# schematic_easyeda.net
KiCad netlist of a schematic drawn in EasyEDA
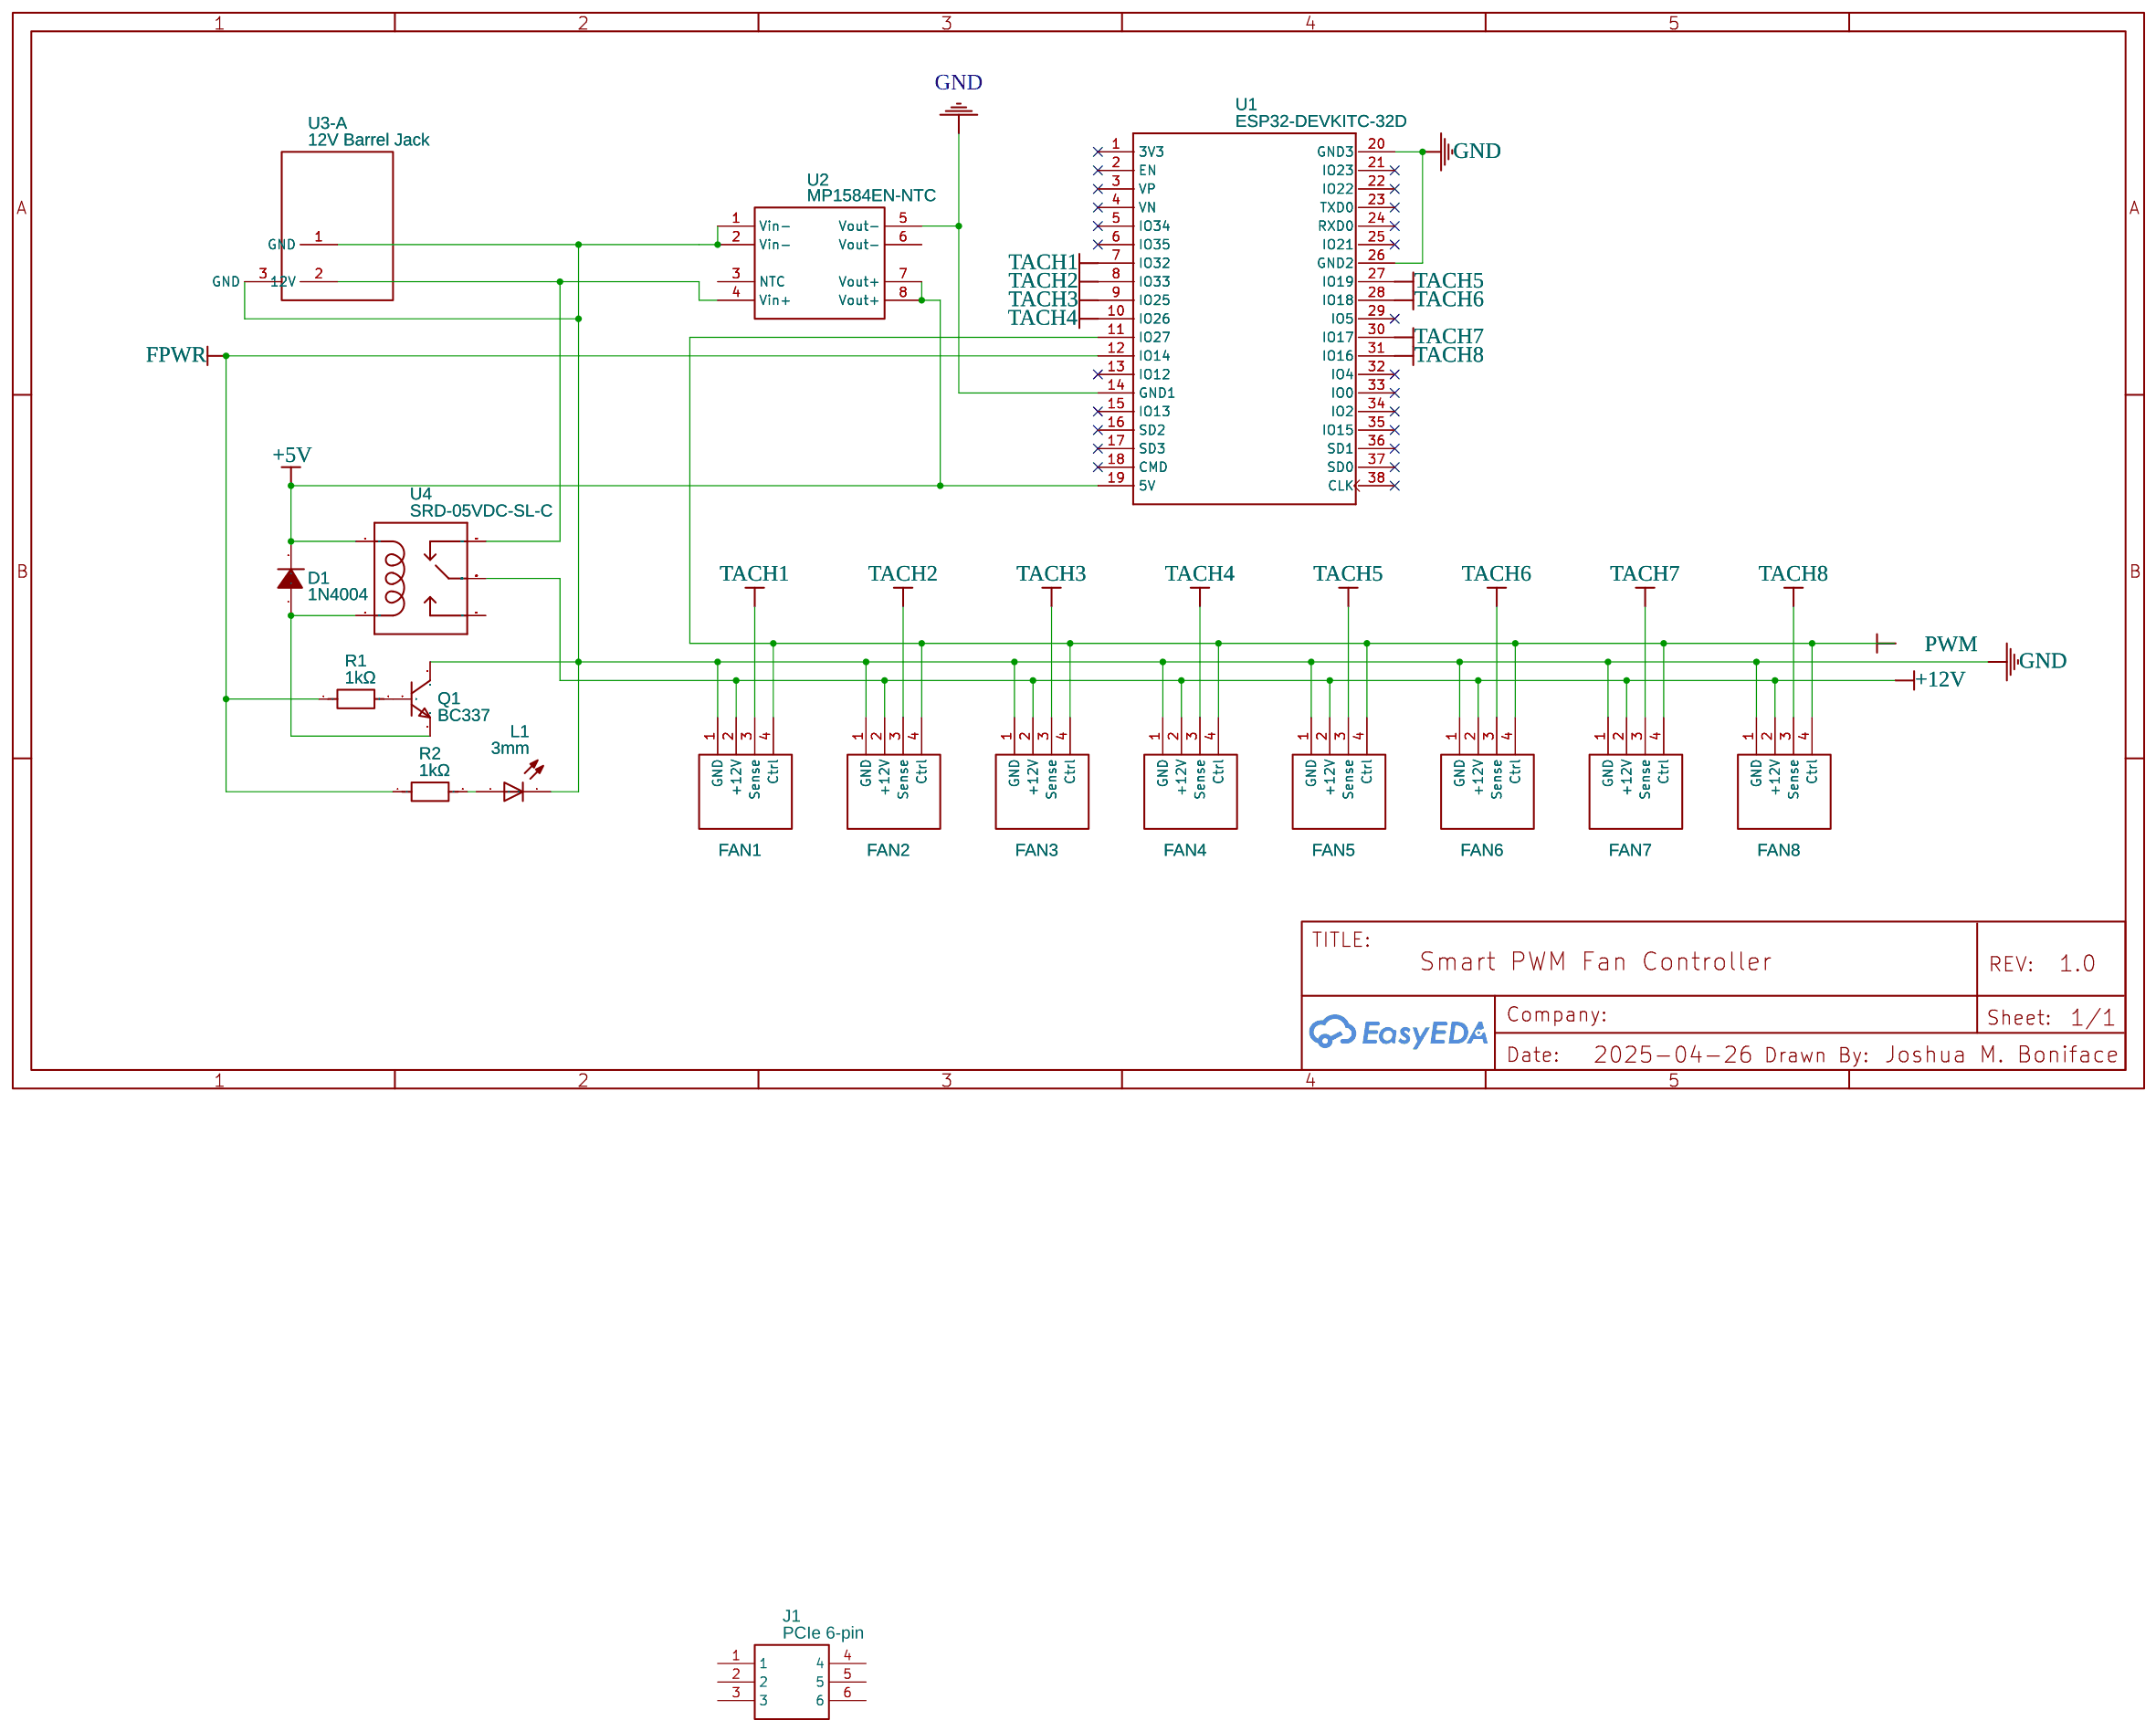
[diagram p0: schematic sheet]

(export (version "E")
  (design (tool "Eeschema 10.0.6"))
  (components
    (comp (ref "D1")
      (value "1N4004")
      (fields (field (name "Manufacturer Part") "1N4007") (field (name "Manufacturer") "ST(先科)"))
      (libsource (lib "") (part "1N4007"))
    )
    (comp (ref "FAN1") (value "4 Pin PWM Fan Header") (libsource (lib "") (part "4 Pin PWM Fan Header")))
    (comp (ref "FAN2") (value "4 Pin PWM Fan Header") (libsource (lib "") (part "4 Pin PWM Fan Header")))
    (comp (ref "FAN3") (value "4 Pin PWM Fan Header") (libsource (lib "") (part "4 Pin PWM Fan Header")))
    (comp (ref "FAN4") (value "4 Pin PWM Fan Header") (libsource (lib "") (part "4 Pin PWM Fan Header")))
    (comp (ref "FAN5") (value "4 Pin PWM Fan Header") (libsource (lib "") (part "4 Pin PWM Fan Header")))
    (comp (ref "FAN6") (value "4 Pin PWM Fan Header") (libsource (lib "") (part "4 Pin PWM Fan Header")))
    (comp (ref "FAN7") (value "4 Pin PWM Fan Header") (libsource (lib "") (part "4 Pin PWM Fan Header")))
    (comp (ref "FAN8") (value "4 Pin PWM Fan Header") (libsource (lib "") (part "4 Pin PWM Fan Header")))
    (comp (ref "J1") (value "PCIe 6-pin") (libsource (lib "") (part "PCIe 6-pin")))
    (comp (ref "L1") (value "3mm") (libsource (lib "") (part "LED 3MM")))
    (comp (ref "Q1")
      (value "BC337")
      (fields (field (name "Manufacturer Part") "2N2222A") (field (name "Manufacturer") "ST(先科)"))
      (libsource (lib "") (part "2N2222"))
    )
    (comp (ref "R1") (value "1kΩ") (libsource (lib "") (part "1/4 W Resistor Vertical")))
    (comp (ref "R2") (value "1kΩ") (libsource (lib "") (part "1/4 W Resistor Vertical")))
    (comp (ref "U1") (value "ESP32-DEVKITC-32D") (libsource (lib "") (part "ESP32-DEVKITC-32D HAT TEMPLATE")))
    (comp (ref "U2")
      (value "MP1584EN-NTC")
      (fields (field (name "Manufacturer Part") "MP1584EN"))
      (libsource (lib "") (part "MP1584EN-NTC COPY"))
    )
    (comp (ref "U3-A") (value "12V Barrel Jack") (libsource (lib "") (part "12V Barrel Jack")))
    (comp (ref "U4") (value "SRD-05VDC-SL-C") (libsource (lib "") (part "12V RELAY")))
  )
  (nets
    (net (code "1") (name "+5V") (class "Default")
      (node (ref "D1") (pin "2") (pinfunction "K_2") (pintype "unspecified"))
      (node (ref "U1") (pin "19") (pinfunction "5V_19") (pintype "bidirectional"))
      (node (ref "U2") (pin "7") (pinfunction "Vout+_7") (pintype "unspecified"))
      (node (ref "U2") (pin "8") (pinfunction "Vout+_8") (pintype "unspecified"))
      (node (ref "U4") (pin "COIL1") (pinfunction "COIL1_COIL1") (pintype "unspecified"))
    )
    (net (code "2") (name "+12V") (class "Default")
      (node (ref "FAN1") (pin "2") (pinfunction "+12V_2") (pintype "unspecified"))
      (node (ref "FAN2") (pin "2") (pinfunction "+12V_2") (pintype "unspecified"))
      (node (ref "FAN3") (pin "2") (pinfunction "+12V_2") (pintype "unspecified"))
      (node (ref "FAN4") (pin "2") (pinfunction "+12V_2") (pintype "unspecified"))
      (node (ref "FAN5") (pin "2") (pinfunction "+12V_2") (pintype "unspecified"))
      (node (ref "FAN6") (pin "2") (pinfunction "+12V_2") (pintype "unspecified"))
      (node (ref "FAN7") (pin "2") (pinfunction "+12V_2") (pintype "unspecified"))
      (node (ref "FAN8") (pin "2") (pinfunction "+12V_2") (pintype "unspecified"))
      (node (ref "U4") (pin "SWCOMMON") (pinfunction "SWCOMMON_SWCOMMON") (pintype "unspecified"))
    )
    (net (code "3") (name "FPWR") (class "Default")
      (node (ref "R1") (pin "1") (pinfunction "1_1") (pintype "unspecified"))
      (node (ref "R2") (pin "1") (pinfunction "1_1") (pintype "unspecified"))
      (node (ref "U1") (pin "12") (pinfunction "IO14_12") (pintype "bidirectional"))
    )
    (net (code "4") (name "GND") (class "Default")
      (node (ref "FAN1") (pin "1") (pinfunction "GND_1") (pintype "unspecified"))
      (node (ref "FAN2") (pin "1") (pinfunction "GND_1") (pintype "unspecified"))
      (node (ref "FAN3") (pin "1") (pinfunction "GND_1") (pintype "unspecified"))
      (node (ref "FAN4") (pin "1") (pinfunction "GND_1") (pintype "unspecified"))
      (node (ref "FAN5") (pin "1") (pinfunction "GND_1") (pintype "unspecified"))
      (node (ref "FAN6") (pin "1") (pinfunction "GND_1") (pintype "unspecified"))
      (node (ref "FAN7") (pin "1") (pinfunction "GND_1") (pintype "unspecified"))
      (node (ref "FAN8") (pin "1") (pinfunction "GND_1") (pintype "unspecified"))
      (node (ref "L1") (pin "K") (pinfunction "2_K") (pintype "unspecified"))
      (node (ref "Q1") (pin "3") (pinfunction "C_3") (pintype "unspecified"))
      (node (ref "U1") (pin "14") (pinfunction "GND1_14") (pintype "bidirectional"))
      (node (ref "U1") (pin "20") (pinfunction "GND3_20") (pintype "bidirectional"))
      (node (ref "U1") (pin "26") (pinfunction "GND2_26") (pintype "bidirectional"))
      (node (ref "U2") (pin "1") (pinfunction "Vin-_1") (pintype "unspecified"))
      (node (ref "U2") (pin "2") (pinfunction "Vin-_2") (pintype "unspecified"))
      (node (ref "U2") (pin "5") (pinfunction "Vout-_5") (pintype "unspecified"))
      (node (ref "U3-A") (pin "1") (pinfunction "GND_1") (pintype "unspecified"))
    )
    (net (code "5") (name "Net-(D1-A)") (class "Default")
      (node (ref "D1") (pin "1") (pinfunction "A_1") (pintype "unspecified"))
      (node (ref "Q1") (pin "1") (pinfunction "E_1") (pintype "unspecified"))
      (node (ref "U4") (pin "COIL0") (pinfunction "COIL0_COIL0") (pintype "unspecified"))
    )
    (net (code "6") (name "Net-(L1-1)") (class "Default")
      (node (ref "L1") (pin "A") (pinfunction "1_A") (pintype "unspecified"))
      (node (ref "R2") (pin "2") (pinfunction "2_2") (pintype "unspecified"))
    )
    (net (code "7") (name "Net-(Q1-B)") (class "Default")
      (node (ref "Q1") (pin "2") (pinfunction "B_2") (pintype "unspecified"))
      (node (ref "R1") (pin "2") (pinfunction "2_2") (pintype "unspecified"))
    )
    (net (code "8") (name "Net-(U2-Vin+)") (class "Default")
      (node (ref "U2") (pin "4") (pinfunction "Vin+_4") (pintype "unspecified"))
      (node (ref "U3-A") (pin "2") (pinfunction "12V_2") (pintype "unspecified"))
      (node (ref "U4") (pin "SWCLOSED") (pinfunction "SWCLOSE_SWCLOSED") (pintype "unspecified"))
    )
    (net (code "9") (name "PWM") (class "Default")
      (node (ref "FAN1") (pin "4") (pinfunction "Ctrl_4") (pintype "unspecified"))
      (node (ref "FAN2") (pin "4") (pinfunction "Ctrl_4") (pintype "unspecified"))
      (node (ref "FAN3") (pin "4") (pinfunction "Ctrl_4") (pintype "unspecified"))
      (node (ref "FAN4") (pin "4") (pinfunction "Ctrl_4") (pintype "unspecified"))
      (node (ref "FAN5") (pin "4") (pinfunction "Ctrl_4") (pintype "unspecified"))
      (node (ref "FAN6") (pin "4") (pinfunction "Ctrl_4") (pintype "unspecified"))
      (node (ref "FAN7") (pin "4") (pinfunction "Ctrl_4") (pintype "unspecified"))
      (node (ref "FAN8") (pin "4") (pinfunction "Ctrl_4") (pintype "unspecified"))
      (node (ref "U1") (pin "11") (pinfunction "IO27_11") (pintype "bidirectional"))
    )
    (net (code "10") (name "TACH1") (class "Default")
      (node (ref "FAN1") (pin "3") (pinfunction "Sense_3") (pintype "unspecified"))
      (node (ref "U1") (pin "7") (pinfunction "IO32_7") (pintype "bidirectional"))
    )
    (net (code "11") (name "TACH2") (class "Default")
      (node (ref "FAN2") (pin "3") (pinfunction "Sense_3") (pintype "unspecified"))
      (node (ref "U1") (pin "8") (pinfunction "IO33_8") (pintype "bidirectional"))
    )
    (net (code "12") (name "TACH3") (class "Default")
      (node (ref "FAN3") (pin "3") (pinfunction "Sense_3") (pintype "unspecified"))
      (node (ref "U1") (pin "9") (pinfunction "IO25_9") (pintype "bidirectional"))
    )
    (net (code "13") (name "TACH4") (class "Default")
      (node (ref "FAN4") (pin "3") (pinfunction "Sense_3") (pintype "unspecified"))
      (node (ref "U1") (pin "10") (pinfunction "IO26_10") (pintype "bidirectional"))
    )
    (net (code "14") (name "TACH5") (class "Default")
      (node (ref "FAN5") (pin "3") (pinfunction "Sense_3") (pintype "unspecified"))
      (node (ref "U1") (pin "27") (pinfunction "IO19_27") (pintype "bidirectional"))
    )
    (net (code "15") (name "TACH6") (class "Default")
      (node (ref "FAN6") (pin "3") (pinfunction "Sense_3") (pintype "unspecified"))
      (node (ref "U1") (pin "28") (pinfunction "IO18_28") (pintype "bidirectional"))
    )
    (net (code "16") (name "TACH7") (class "Default")
      (node (ref "FAN7") (pin "3") (pinfunction "Sense_3") (pintype "unspecified"))
      (node (ref "U1") (pin "30") (pinfunction "IO17_30") (pintype "bidirectional"))
    )
    (net (code "17") (name "TACH8") (class "Default")
      (node (ref "FAN8") (pin "3") (pinfunction "Sense_3") (pintype "unspecified"))
      (node (ref "U1") (pin "31") (pinfunction "IO16_31") (pintype "bidirectional"))
    )
    (net (code "18") (name "unconnected-(J1-Pad1)") (class "Default")
      (node (ref "J1") (pin "1") (pinfunction "1_1") (pintype "unspecified"))
    )
    (net (code "19") (name "unconnected-(J1-Pad2)") (class "Default")
      (node (ref "J1") (pin "2") (pinfunction "2_2") (pintype "unspecified"))
    )
    (net (code "20") (name "unconnected-(J1-Pad3)") (class "Default")
      (node (ref "J1") (pin "3") (pinfunction "3_3") (pintype "unspecified"))
    )
    (net (code "21") (name "unconnected-(J1-Pad4)") (class "Default")
      (node (ref "J1") (pin "4") (pinfunction "4_4") (pintype "unspecified"))
    )
    (net (code "22") (name "unconnected-(J1-Pad5)") (class "Default")
      (node (ref "J1") (pin "5") (pinfunction "5_5") (pintype "unspecified"))
    )
    (net (code "23") (name "unconnected-(J1-Pad6)") (class "Default")
      (node (ref "J1") (pin "6") (pinfunction "6_6") (pintype "unspecified"))
    )
    (net (code "24") (name "unconnected-(U1-3V3-Pad1)") (class "Default")
      (node (ref "U1") (pin "1") (pinfunction "3V3_1") (pintype "bidirectional+no_connect"))
    )
    (net (code "25") (name "unconnected-(U1-CLK-Pad38)") (class "Default")
      (node (ref "U1") (pin "38") (pinfunction "CLK_38") (pintype "bidirectional+no_connect"))
    )
    (net (code "26") (name "unconnected-(U1-CMD-Pad18)") (class "Default")
      (node (ref "U1") (pin "18") (pinfunction "CMD_18") (pintype "bidirectional+no_connect"))
    )
    (net (code "27") (name "unconnected-(U1-EN-Pad2)") (class "Default")
      (node (ref "U1") (pin "2") (pinfunction "EN_2") (pintype "bidirectional+no_connect"))
    )
    (net (code "28") (name "unconnected-(U1-IO0-Pad33)") (class "Default")
      (node (ref "U1") (pin "33") (pinfunction "IO0_33") (pintype "bidirectional+no_connect"))
    )
    (net (code "29") (name "unconnected-(U1-IO2-Pad34)") (class "Default")
      (node (ref "U1") (pin "34") (pinfunction "IO2_34") (pintype "bidirectional+no_connect"))
    )
    (net (code "30") (name "unconnected-(U1-IO4-Pad32)") (class "Default")
      (node (ref "U1") (pin "32") (pinfunction "IO4_32") (pintype "bidirectional+no_connect"))
    )
    (net (code "31") (name "unconnected-(U1-IO5-Pad29)") (class "Default")
      (node (ref "U1") (pin "29") (pinfunction "IO5_29") (pintype "bidirectional+no_connect"))
    )
    (net (code "32") (name "unconnected-(U1-IO12-Pad13)") (class "Default")
      (node (ref "U1") (pin "13") (pinfunction "IO12_13") (pintype "bidirectional+no_connect"))
    )
    (net (code "33") (name "unconnected-(U1-IO13-Pad15)") (class "Default")
      (node (ref "U1") (pin "15") (pinfunction "IO13_15") (pintype "bidirectional+no_connect"))
    )
    (net (code "34") (name "unconnected-(U1-IO15-Pad35)") (class "Default")
      (node (ref "U1") (pin "35") (pinfunction "IO15_35") (pintype "bidirectional+no_connect"))
    )
    (net (code "35") (name "unconnected-(U1-IO21-Pad25)") (class "Default")
      (node (ref "U1") (pin "25") (pinfunction "IO21_25") (pintype "bidirectional+no_connect"))
    )
    (net (code "36") (name "unconnected-(U1-IO22-Pad22)") (class "Default")
      (node (ref "U1") (pin "22") (pinfunction "IO22_22") (pintype "bidirectional+no_connect"))
    )
    (net (code "37") (name "unconnected-(U1-IO23-Pad21)") (class "Default")
      (node (ref "U1") (pin "21") (pinfunction "IO23_21") (pintype "bidirectional+no_connect"))
    )
    (net (code "38") (name "unconnected-(U1-IO34-Pad5)") (class "Default")
      (node (ref "U1") (pin "5") (pinfunction "IO34_5") (pintype "bidirectional+no_connect"))
    )
    (net (code "39") (name "unconnected-(U1-IO35-Pad6)") (class "Default")
      (node (ref "U1") (pin "6") (pinfunction "IO35_6") (pintype "bidirectional+no_connect"))
    )
    (net (code "40") (name "unconnected-(U1-RXD0-Pad24)") (class "Default")
      (node (ref "U1") (pin "24") (pinfunction "RXD0_24") (pintype "bidirectional+no_connect"))
    )
    (net (code "41") (name "unconnected-(U1-SD0-Pad37)") (class "Default")
      (node (ref "U1") (pin "37") (pinfunction "SD0_37") (pintype "bidirectional+no_connect"))
    )
    (net (code "42") (name "unconnected-(U1-SD1-Pad36)") (class "Default")
      (node (ref "U1") (pin "36") (pinfunction "SD1_36") (pintype "bidirectional+no_connect"))
    )
    (net (code "43") (name "unconnected-(U1-SD2-Pad16)") (class "Default")
      (node (ref "U1") (pin "16") (pinfunction "SD2_16") (pintype "bidirectional+no_connect"))
    )
    (net (code "44") (name "unconnected-(U1-SD3-Pad17)") (class "Default")
      (node (ref "U1") (pin "17") (pinfunction "SD3_17") (pintype "bidirectional+no_connect"))
    )
    (net (code "45") (name "unconnected-(U1-TXD0-Pad23)") (class "Default")
      (node (ref "U1") (pin "23") (pinfunction "TXD0_23") (pintype "bidirectional+no_connect"))
    )
    (net (code "46") (name "unconnected-(U1-VN-Pad4)") (class "Default")
      (node (ref "U1") (pin "4") (pinfunction "VN_4") (pintype "bidirectional+no_connect"))
    )
    (net (code "47") (name "unconnected-(U1-VP-Pad3)") (class "Default")
      (node (ref "U1") (pin "3") (pinfunction "VP_3") (pintype "bidirectional+no_connect"))
    )
    (net (code "48") (name "unconnected-(U2-NTC-Pad3)") (class "Default")
      (node (ref "U2") (pin "3") (pinfunction "NTC_3") (pintype "unspecified"))
    )
    (net (code "49") (name "unconnected-(U2-Vout--Pad6)") (class "Default")
      (node (ref "U2") (pin "6") (pinfunction "Vout-_6") (pintype "unspecified"))
    )
    (net (code "50") (name "unconnected-(U3-A-GND-Pad3)") (class "Default")
      (node (ref "U3-A") (pin "3") (pinfunction "GND_3") (pintype "unspecified"))
    )
    (net (code "51") (name "unconnected-(U4-PadSWOPEN)") (class "Default")
      (node (ref "U4") (pin "SWOPEN") (pinfunction "SWOPEN_SWOPEN") (pintype "unspecified"))
    )
  )
)
